# Thermometers.net
KiCad netlist of a schematic drawn in Altium Designer
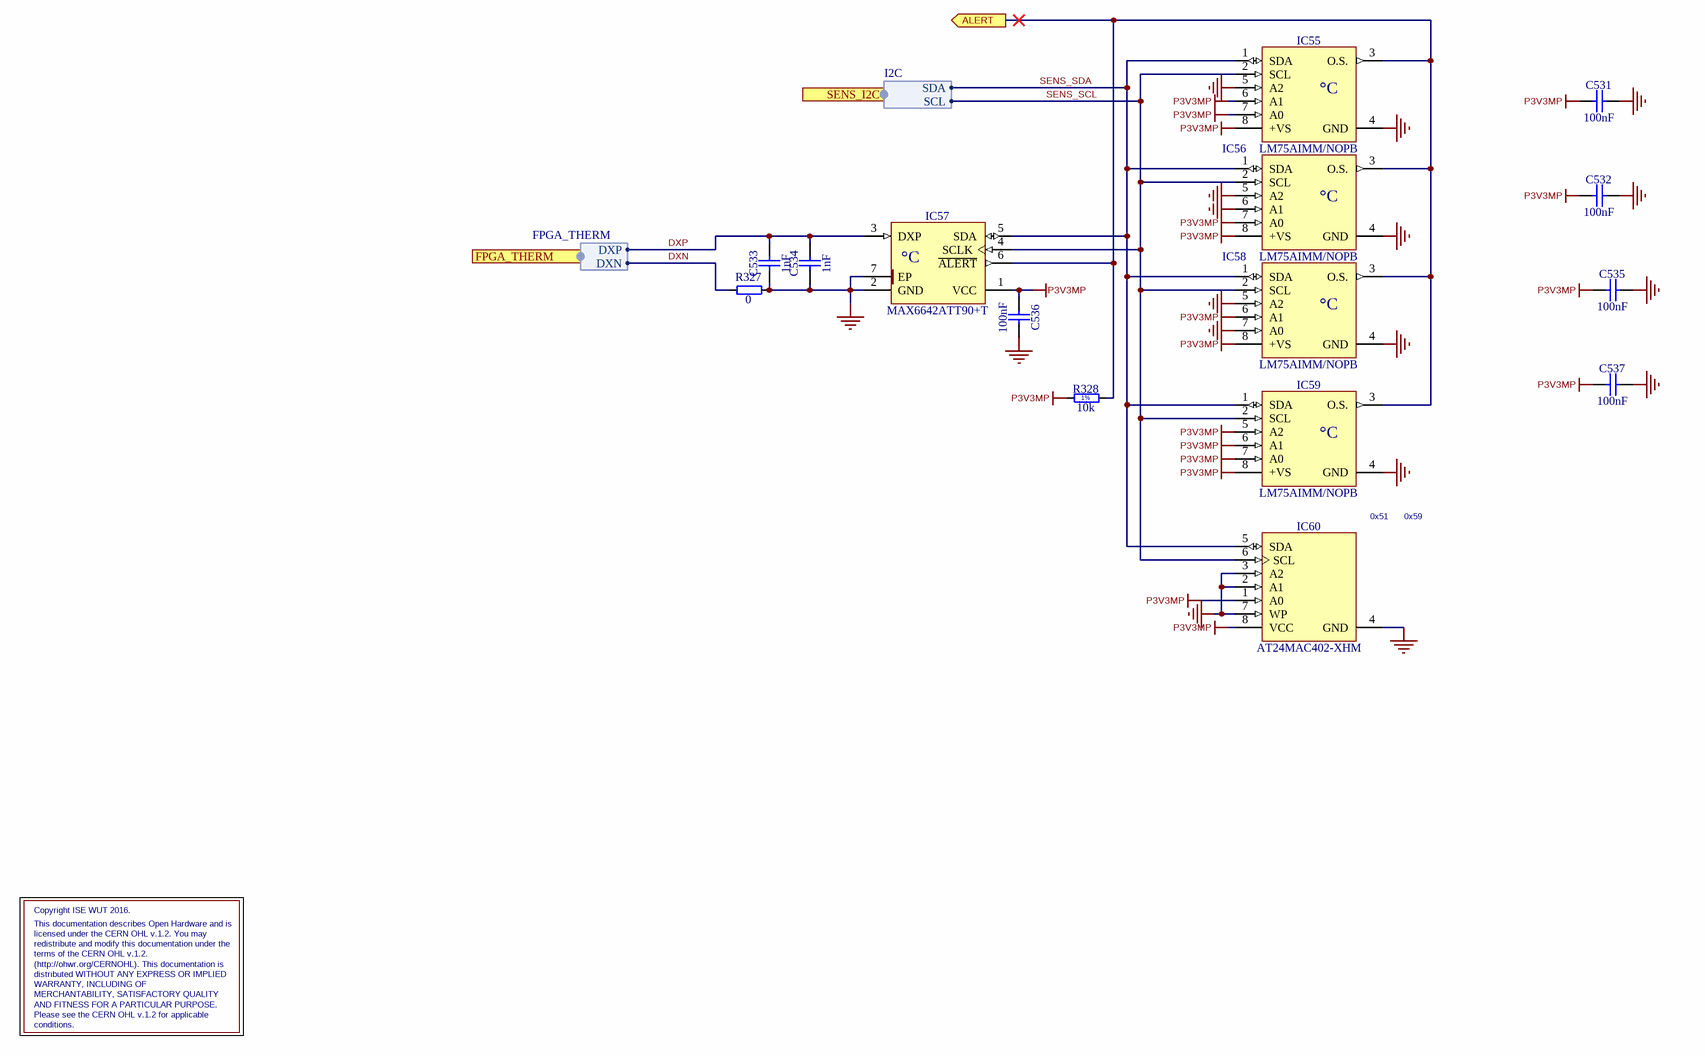
[diagram p0: Thermometers.SchDoc]

(export (version "E")
  (design (tool "Eeschema 10.0.6"))
  (components
    (comp (ref "C531")
      (value "100nF")
      (footprint "CAPC0603X33N")
      (description "Non-polarised capacitor")
      (fields
        (field (name "MANUFACTURER PART NUMBER") "CC0201_100NF_6.3V_10%_X5R")
        (field (name "MANUFACTURER") "GENERIC")
        (field (name "AUTHOR") "CERN DEM JLC")
      )
      (libsource (lib "Capacitors") (part "Capacitor - non polarized"))
    )
    (comp (ref "C532")
      (value "100nF")
      (footprint "CAPC0603X33N")
      (description "Non-polarised capacitor")
      (fields
        (field (name "MANUFACTURER PART NUMBER") "CC0201_100NF_6.3V_10%_X5R")
        (field (name "MANUFACTURER") "GENERIC")
        (field (name "AUTHOR") "CERN DEM JLC")
      )
      (libsource (lib "Capacitors") (part "Capacitor - non polarized"))
    )
    (comp (ref "C533")
      (value "1nF")
      (footprint "CAPC1005X55N")
      (description "Non-polarised capacitor")
      (fields
        (field (name "MANUFACTURER PART NUMBER") "CC0402_1NF_50V_10%_X7R")
        (field (name "MANUFACTURER") "GENERIC")
        (field (name "AUTHOR") "CERN DEM JLC")
      )
      (libsource (lib "Capacitors") (part "Capacitor - non polarized"))
    )
    (comp (ref "C534")
      (value "1nF")
      (footprint "CAPC1005X55N")
      (description "Non-polarised capacitor")
      (fields
        (field (name "MANUFACTURER PART NUMBER") "CC0402_1NF_50V_10%_X7R")
        (field (name "MANUFACTURER") "GENERIC")
        (field (name "AUTHOR") "CERN DEM JLC")
      )
      (libsource (lib "Capacitors") (part "Capacitor - non polarized"))
    )
    (comp (ref "C535")
      (value "100nF")
      (footprint "CAPC0603X33N")
      (description "Non-polarised capacitor")
      (fields
        (field (name "MANUFACTURER PART NUMBER") "CC0201_100NF_6.3V_10%_X5R")
        (field (name "MANUFACTURER") "GENERIC")
        (field (name "AUTHOR") "CERN DEM JLC")
      )
      (libsource (lib "Capacitors") (part "Capacitor - non polarized"))
    )
    (comp (ref "C536")
      (value "100nF")
      (footprint "CAPC0603X33N")
      (description "Non-polarised capacitor")
      (fields
        (field (name "MANUFACTURER PART NUMBER") "CC0201_100NF_6.3V_10%_X5R")
        (field (name "MANUFACTURER") "GENERIC")
        (field (name "AUTHOR") "CERN DEM JLC")
      )
      (libsource (lib "Capacitors") (part "Capacitor - non polarized"))
    )
    (comp (ref "C537")
      (value "100nF")
      (footprint "CAPC0603X33N")
      (description "Non-polarised capacitor")
      (fields
        (field (name "MANUFACTURER PART NUMBER") "CC0201_100NF_6.3V_10%_X5R")
        (field (name "MANUFACTURER") "GENERIC")
        (field (name "AUTHOR") "CERN DEM JLC")
      )
      (libsource (lib "Capacitors") (part "Capacitor - non polarized"))
    )
    (comp (ref "IC55")
      (value "LM75AIMM/NOPB")
      (footprint "SOP65P490X109-8N")
      (description "Digital Temperature Sensor and Thermal Watchdog with Two-Wire Interface")
      (fields (field (name "MANUFACTURER") "TEXAS INSTRUMENTS") (field (name "AUTHOR") "CERN DEM JLC"))
      (libsource (lib "ICs And Semiconductors") (part "LM75"))
    )
    (comp (ref "IC56")
      (value "LM75AIMM/NOPB")
      (footprint "SOP65P490X109-8N")
      (description "Digital Temperature Sensor and Thermal Watchdog with Two-Wire Interface")
      (fields (field (name "MANUFACTURER") "TEXAS INSTRUMENTS") (field (name "AUTHOR") "CERN DEM JLC"))
      (libsource (lib "ICs And Semiconductors") (part "LM75"))
    )
    (comp (ref "IC57")
      (value "MAX6642ATT90+T")
      (footprint "SON95P300X300X80-7N-R160X240")
      (description "±1°C, SMBus-Compatible Remote/Local Temperature Sensor with Overtemperature Alarm")
      (fields (field (name "MANUFACTURER") "MAXIM") (field (name "AUTHOR") "CERN DEM JLC"))
      (libsource (lib "ICs And Semiconductors") (part "MAX6642ATT"))
    )
    (comp (ref "IC58")
      (value "LM75AIMM/NOPB")
      (footprint "SOP65P490X109-8N")
      (description "Digital Temperature Sensor and Thermal Watchdog with Two-Wire Interface")
      (fields (field (name "MANUFACTURER") "TEXAS INSTRUMENTS") (field (name "AUTHOR") "CERN DEM JLC"))
      (libsource (lib "ICs And Semiconductors") (part "LM75"))
    )
    (comp (ref "IC59")
      (value "LM75AIMM/NOPB")
      (footprint "SOP65P490X109-8N")
      (description "Digital Temperature Sensor and Thermal Watchdog with Two-Wire Interface")
      (fields (field (name "MANUFACTURER") "TEXAS INSTRUMENTS") (field (name "AUTHOR") "CERN DEM JLC"))
      (libsource (lib "ICs And Semiconductors") (part "LM75"))
    )
    (comp (ref "IC60")
      (value "AT24MAC402-XHM")
      (footprint "SOP65P640X120-8N")
      (description "1.7V to 5.5V, I2C-Compatible (2-wire) 2-Kbit (256 x 8) Serial EEPROM")
      (fields (field (name "MANUFACTURER") "ATMEL") (field (name "AUTHOR") "CERN DEM MR"))
      (libsource (lib "ICs And Semiconductors") (part "AT24MAC402-XHM"))
    )
    (comp (ref "R327")
      (value "0")
      (footprint "RESC1005X40N")
      (description "Resistor")
      (fields
        (field (name "MANUFACTURER PART NUMBER") "R0402_0R_JUMPER")
        (field (name "MANUFACTURER") "GENERIC")
        (field (name "AUTHOR") "CERN DEM JLC")
      )
      (libsource (lib "Resistors") (part "Resistor"))
    )
    (comp (ref "R328")
      (value "10k")
      (footprint "RESC1005X40N")
      (description "Resistor - 1%")
      (fields
        (field (name "MANUFACTURER PART NUMBER") "R0402_10K_1%_0.0625W_100PPM")
        (field (name "MANUFACTURER") "GENERIC")
        (field (name "AUTHOR") "CERN DEM JLC")
      )
      (libsource (lib "Resistors") (part "Resistor - 1%"))
    )
  )
  (nets
    (net (code "3") (name "/ALERT") (class "Default")
      (node (ref "IC55") (pin "3") (pinfunction "O.S._3") (pintype "output"))
      (node (ref "IC56") (pin "3") (pinfunction "O.S._3") (pintype "output"))
      (node (ref "IC57") (pin "6") (pinfunction "~{ALERT}_6") (pintype "output"))
      (node (ref "IC58") (pin "3") (pinfunction "O.S._3") (pintype "output"))
      (node (ref "IC59") (pin "3") (pinfunction "O.S._3") (pintype "output"))
      (node (ref "R328") (pin "2") (pinfunction "2_2") (pintype "passive"))
    )
    (net (code "4") (name "/DXN") (class "Default")
      (node (ref "R327") (pin "1") (pinfunction "1_1") (pintype "passive"))
    )
    (net (code "5") (name "/DXP") (class "Default")
      (node (ref "C533") (pin "2") (pinfunction "2_2") (pintype "passive"))
      (node (ref "C534") (pin "2") (pinfunction "2_2") (pintype "passive"))
      (node (ref "IC57") (pin "3") (pinfunction "DXP_3") (pintype "input"))
    )
    (net (code "6") (name "/SENS_SCL") (class "Default")
      (node (ref "IC55") (pin "2") (pinfunction "SCL_2") (pintype "input"))
      (node (ref "IC56") (pin "2") (pinfunction "SCL_2") (pintype "input"))
      (node (ref "IC57") (pin "4") (pinfunction "SCLK_4") (pintype "input"))
      (node (ref "IC58") (pin "2") (pinfunction "SCL_2") (pintype "input"))
      (node (ref "IC59") (pin "2") (pinfunction "SCL_2") (pintype "input"))
      (node (ref "IC60") (pin "6") (pinfunction "SCL_6") (pintype "input"))
    )
    (net (code "7") (name "/SENS_SDA") (class "Default")
      (node (ref "IC55") (pin "1") (pinfunction "SDA_1") (pintype "bidirectional"))
      (node (ref "IC56") (pin "1") (pinfunction "SDA_1") (pintype "bidirectional"))
      (node (ref "IC57") (pin "5") (pinfunction "SDA_5") (pintype "bidirectional"))
      (node (ref "IC58") (pin "1") (pinfunction "SDA_1") (pintype "bidirectional"))
      (node (ref "IC59") (pin "1") (pinfunction "SDA_1") (pintype "bidirectional"))
      (node (ref "IC60") (pin "5") (pinfunction "SDA_5") (pintype "bidirectional"))
    )
    (net (code "10") (name "GND") (class "Default")
      (node (ref "C531") (pin "2") (pinfunction "2_2") (pintype "passive"))
      (node (ref "C532") (pin "2") (pinfunction "2_2") (pintype "passive"))
      (node (ref "C533") (pin "1") (pinfunction "1_1") (pintype "passive"))
      (node (ref "C534") (pin "1") (pinfunction "1_1") (pintype "passive"))
      (node (ref "C535") (pin "2") (pinfunction "2_2") (pintype "passive"))
      (node (ref "C536") (pin "1") (pinfunction "1_1") (pintype "passive"))
      (node (ref "C537") (pin "2") (pinfunction "2_2") (pintype "passive"))
      (node (ref "IC55") (pin "4") (pinfunction "GND_4") (pintype "power_in"))
      (node (ref "IC55") (pin "5") (pinfunction "A2_5") (pintype "input"))
      (node (ref "IC56") (pin "4") (pinfunction "GND_4") (pintype "power_in"))
      (node (ref "IC56") (pin "5") (pinfunction "A2_5") (pintype "input"))
      (node (ref "IC56") (pin "6") (pinfunction "A1_6") (pintype "input"))
      (node (ref "IC57") (pin "2") (pinfunction "GND_2") (pintype "power_in"))
      (node (ref "IC57") (pin "7") (pinfunction "EP_7") (pintype "power_in"))
      (node (ref "IC58") (pin "4") (pinfunction "GND_4") (pintype "power_in"))
      (node (ref "IC58") (pin "5") (pinfunction "A2_5") (pintype "input"))
      (node (ref "IC58") (pin "7") (pinfunction "A0_7") (pintype "input"))
      (node (ref "IC59") (pin "4") (pinfunction "GND_4") (pintype "power_in"))
      (node (ref "IC60") (pin "2") (pinfunction "A1_2") (pintype "input"))
      (node (ref "IC60") (pin "3") (pinfunction "A2_3") (pintype "input"))
      (node (ref "IC60") (pin "4") (pinfunction "GND_4") (pintype "power_in"))
      (node (ref "IC60") (pin "7") (pinfunction "WP_7") (pintype "input"))
      (node (ref "R327") (pin "2") (pinfunction "2_2") (pintype "passive"))
    )
    (net (code "11") (name "P3V3MP") (class "Default")
      (node (ref "C531") (pin "1") (pinfunction "1_1") (pintype "passive"))
      (node (ref "C532") (pin "1") (pinfunction "1_1") (pintype "passive"))
      (node (ref "C535") (pin "1") (pinfunction "1_1") (pintype "passive"))
      (node (ref "C536") (pin "2") (pinfunction "2_2") (pintype "passive"))
      (node (ref "C537") (pin "1") (pinfunction "1_1") (pintype "passive"))
      (node (ref "IC55") (pin "6") (pinfunction "A1_6") (pintype "input"))
      (node (ref "IC55") (pin "7") (pinfunction "A0_7") (pintype "input"))
      (node (ref "IC55") (pin "8") (pinfunction "+VS_8") (pintype "power_in"))
      (node (ref "IC56") (pin "7") (pinfunction "A0_7") (pintype "input"))
      (node (ref "IC56") (pin "8") (pinfunction "+VS_8") (pintype "power_in"))
      (node (ref "IC57") (pin "1") (pinfunction "VCC_1") (pintype "power_in"))
      (node (ref "IC58") (pin "6") (pinfunction "A1_6") (pintype "input"))
      (node (ref "IC58") (pin "8") (pinfunction "+VS_8") (pintype "power_in"))
      (node (ref "IC59") (pin "5") (pinfunction "A2_5") (pintype "input"))
      (node (ref "IC59") (pin "6") (pinfunction "A1_6") (pintype "input"))
      (node (ref "IC59") (pin "7") (pinfunction "A0_7") (pintype "input"))
      (node (ref "IC59") (pin "8") (pinfunction "+VS_8") (pintype "power_in"))
      (node (ref "IC60") (pin "1") (pinfunction "A0_1") (pintype "input"))
      (node (ref "IC60") (pin "8") (pinfunction "VCC_8") (pintype "power_in"))
      (node (ref "R328") (pin "1") (pinfunction "1_1") (pintype "passive"))
    )
  )
)
